# design.net
KiCad netlist of a schematic drawn in Altium Designer
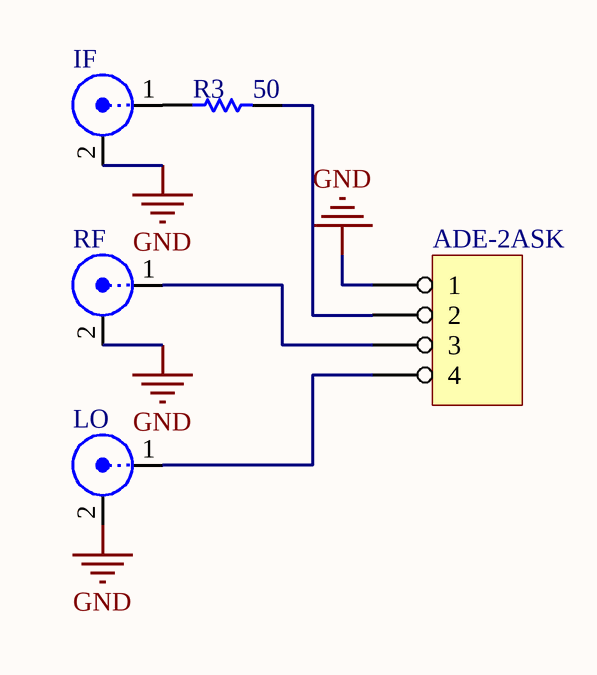
[diagram p0: 混频器.SchDoc]

(export (version "E")
  (design (tool "Eeschema 10.0.6"))
  (components
    (comp (ref "ADE-2ASK")
      (value "4 HEADER")
      (footprint "PL-052")
      (description "4 Pin Header")
      (libsource (lib "ADE-2ASK") (part "4 HEADER"))
    )
    (comp (ref "IF") (value "SMA-2") (footprint "SMA-2") (libsource (lib "SMA-2") (part "SMA-2")))
    (comp (ref "LO") (value "SMA-2") (footprint "SMA-2") (libsource (lib "SMA-2") (part "SMA-2")))
    (comp (ref "R3")
      (value "RES")
      (footprint "0805")
      (fields (field (name "值") "50"))
      (libsource (lib "电源") (part "RES"))
    )
    (comp (ref "RF") (value "SMA-2") (footprint "SMA-2") (libsource (lib "SMA-2") (part "SMA-2")))
  )
  (nets
    (net (code "1") (name "GND") (class "Default")
      (node (ref "ADE-2ASK") (pin "1") (pinfunction "1_1") (pintype "passive"))
      (node (ref "IF") (pin "2") (pinfunction "GND_2") (pintype "passive"))
      (node (ref "LO") (pin "2") (pinfunction "GND_2") (pintype "passive"))
      (node (ref "RF") (pin "2") (pinfunction "GND_2") (pintype "passive"))
    )
    (net (code "2") (name "Net-(ADE-2ASK-Pad2)") (class "Default")
      (node (ref "ADE-2ASK") (pin "2") (pinfunction "2_2") (pintype "passive"))
      (node (ref "R3") (pin "2") (pinfunction "2_2") (pintype "passive"))
    )
    (net (code "3") (name "Net-(IF-Signal)") (class "Default")
      (node (ref "IF") (pin "1") (pinfunction "Signal_1") (pintype "passive"))
      (node (ref "R3") (pin "1") (pinfunction "1_1") (pintype "passive"))
    )
    (net (code "4") (name "Net-(LO-Signal)") (class "Default")
      (node (ref "ADE-2ASK") (pin "4") (pinfunction "4_4") (pintype "passive"))
      (node (ref "LO") (pin "1") (pinfunction "Signal_1") (pintype "passive"))
    )
    (net (code "5") (name "Net-(RF-Signal)") (class "Default")
      (node (ref "ADE-2ASK") (pin "3") (pinfunction "3_3") (pintype "passive"))
      (node (ref "RF") (pin "1") (pinfunction "Signal_1") (pintype "passive"))
    )
  )
)
